# pmod-pass-thru-UNIVERSAL.net
KiCad netlist of a schematic drawn in Altium Designer
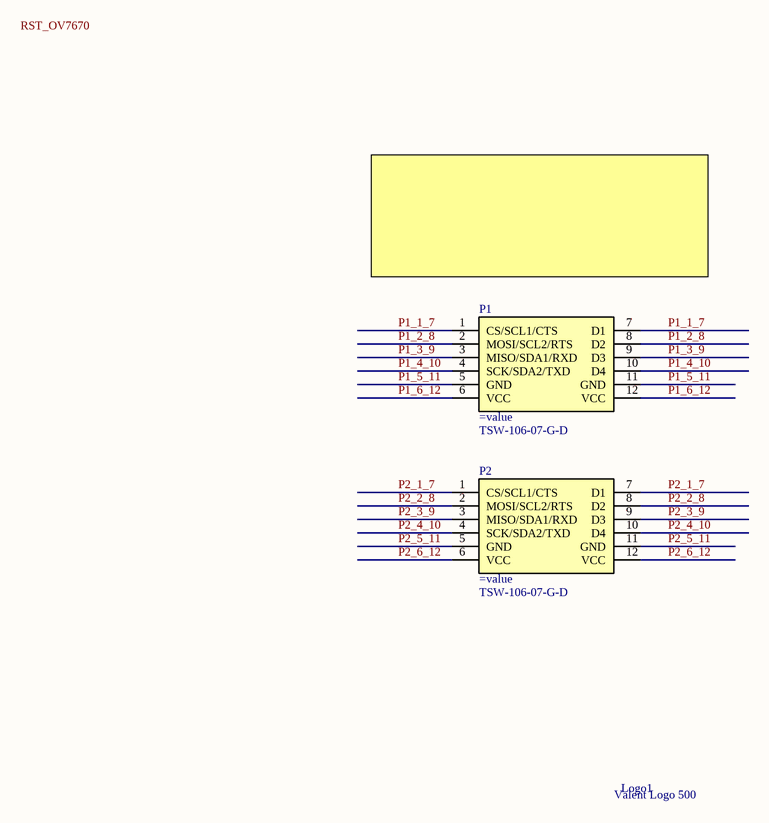
[diagram p0: pmod-pass-thru-UNIVERSAL.SchDoc]

(export (version "E")
  (design (tool "Eeschema 10.0.6"))
  (components
    (comp (ref "Logo1")
      (value "Valent Logo 500")
      (footprint "VALENTFX_500-SolderMask")
      (libsource (lib "mLogos") (part "Valent Logo 500"))
    )
    (comp (ref "P1")
      (value "~")
      (footprint "PMOD-S-TSW-106-07-G-D")
      (description "Conn Unshrouded Header Straight HDR 12 POS 2.54mm Solder ST Thru-Hole Bulk")
      (fields
        (field (name "MANUFACTURER") "Samtec")
        (field (name "MANUFACTURER PART NUMBER") "TSW-106-07-G-D")
        (field (name "SUPPLIER PART NUMBER 1") "TSW-106-07-G-D")
      )
      (libsource (lib "mConnector") (part "PMOD-S-TSW-106-07-G-D"))
    )
    (comp (ref "P2")
      (value "~")
      (footprint "PMOD-S-TSW-106-07-G-D")
      (description "Conn Unshrouded Header Straight HDR 12 POS 2.54mm Solder ST Thru-Hole Bulk")
      (fields
        (field (name "MANUFACTURER") "Samtec")
        (field (name "MANUFACTURER PART NUMBER") "TSW-106-07-G-D")
        (field (name "SUPPLIER PART NUMBER 1") "TSW-106-07-G-D")
      )
      (libsource (lib "mConnector") (part "PMOD-S-TSW-106-07-G-D"))
    )
  )
  (nets
    (net (code "1") (name "/P1_1_7") (class "Default")
      (node (ref "P1") (pin "1") (pinfunction "CS/SCL1/CTS_1") (pintype "power_in"))
      (node (ref "P1") (pin "7") (pinfunction "D1_7") (pintype "power_in"))
    )
    (net (code "2") (name "/P1_2_8") (class "Default")
      (node (ref "P1") (pin "2") (pinfunction "MOSI/SCL2/RTS_2") (pintype "power_in"))
      (node (ref "P1") (pin "8") (pinfunction "D2_8") (pintype "power_in"))
    )
    (net (code "3") (name "/P1_3_9") (class "Default")
      (node (ref "P1") (pin "3") (pinfunction "MISO/SDA1/RXD_3") (pintype "power_in"))
      (node (ref "P1") (pin "9") (pinfunction "D3_9") (pintype "power_in"))
    )
    (net (code "4") (name "/P1_4_10") (class "Default")
      (node (ref "P1") (pin "10") (pinfunction "D4_10") (pintype "power_in"))
      (node (ref "P1") (pin "4") (pinfunction "SCK/SDA2/TXD_4") (pintype "power_in"))
    )
    (net (code "5") (name "/P1_5_11") (class "Default")
      (node (ref "P1") (pin "11") (pinfunction "GND_11") (pintype "power_in"))
      (node (ref "P1") (pin "5") (pinfunction "GND_5") (pintype "power_in"))
    )
    (net (code "6") (name "/P1_6_12") (class "Default")
      (node (ref "P1") (pin "12") (pinfunction "VCC_12") (pintype "power_in"))
      (node (ref "P1") (pin "6") (pinfunction "VCC_6") (pintype "power_in"))
    )
    (net (code "7") (name "/P2_1_7") (class "Default")
      (node (ref "P2") (pin "1") (pinfunction "CS/SCL1/CTS_1") (pintype "power_in"))
      (node (ref "P2") (pin "7") (pinfunction "D1_7") (pintype "power_in"))
    )
    (net (code "8") (name "/P2_2_8") (class "Default")
      (node (ref "P2") (pin "2") (pinfunction "MOSI/SCL2/RTS_2") (pintype "power_in"))
      (node (ref "P2") (pin "8") (pinfunction "D2_8") (pintype "power_in"))
    )
    (net (code "9") (name "/P2_3_9") (class "Default")
      (node (ref "P2") (pin "3") (pinfunction "MISO/SDA1/RXD_3") (pintype "power_in"))
      (node (ref "P2") (pin "9") (pinfunction "D3_9") (pintype "power_in"))
    )
    (net (code "10") (name "/P2_4_10") (class "Default")
      (node (ref "P2") (pin "10") (pinfunction "D4_10") (pintype "power_in"))
      (node (ref "P2") (pin "4") (pinfunction "SCK/SDA2/TXD_4") (pintype "power_in"))
    )
    (net (code "11") (name "/P2_5_11") (class "Default")
      (node (ref "P2") (pin "11") (pinfunction "GND_11") (pintype "power_in"))
      (node (ref "P2") (pin "5") (pinfunction "GND_5") (pintype "power_in"))
    )
    (net (code "12") (name "/P2_6_12") (class "Default")
      (node (ref "P2") (pin "12") (pinfunction "VCC_12") (pintype "power_in"))
      (node (ref "P2") (pin "6") (pinfunction "VCC_6") (pintype "power_in"))
    )
  )
)
